# SyringeDriverHW10.net
KiCad netlist of a schematic drawn in Altium Designer
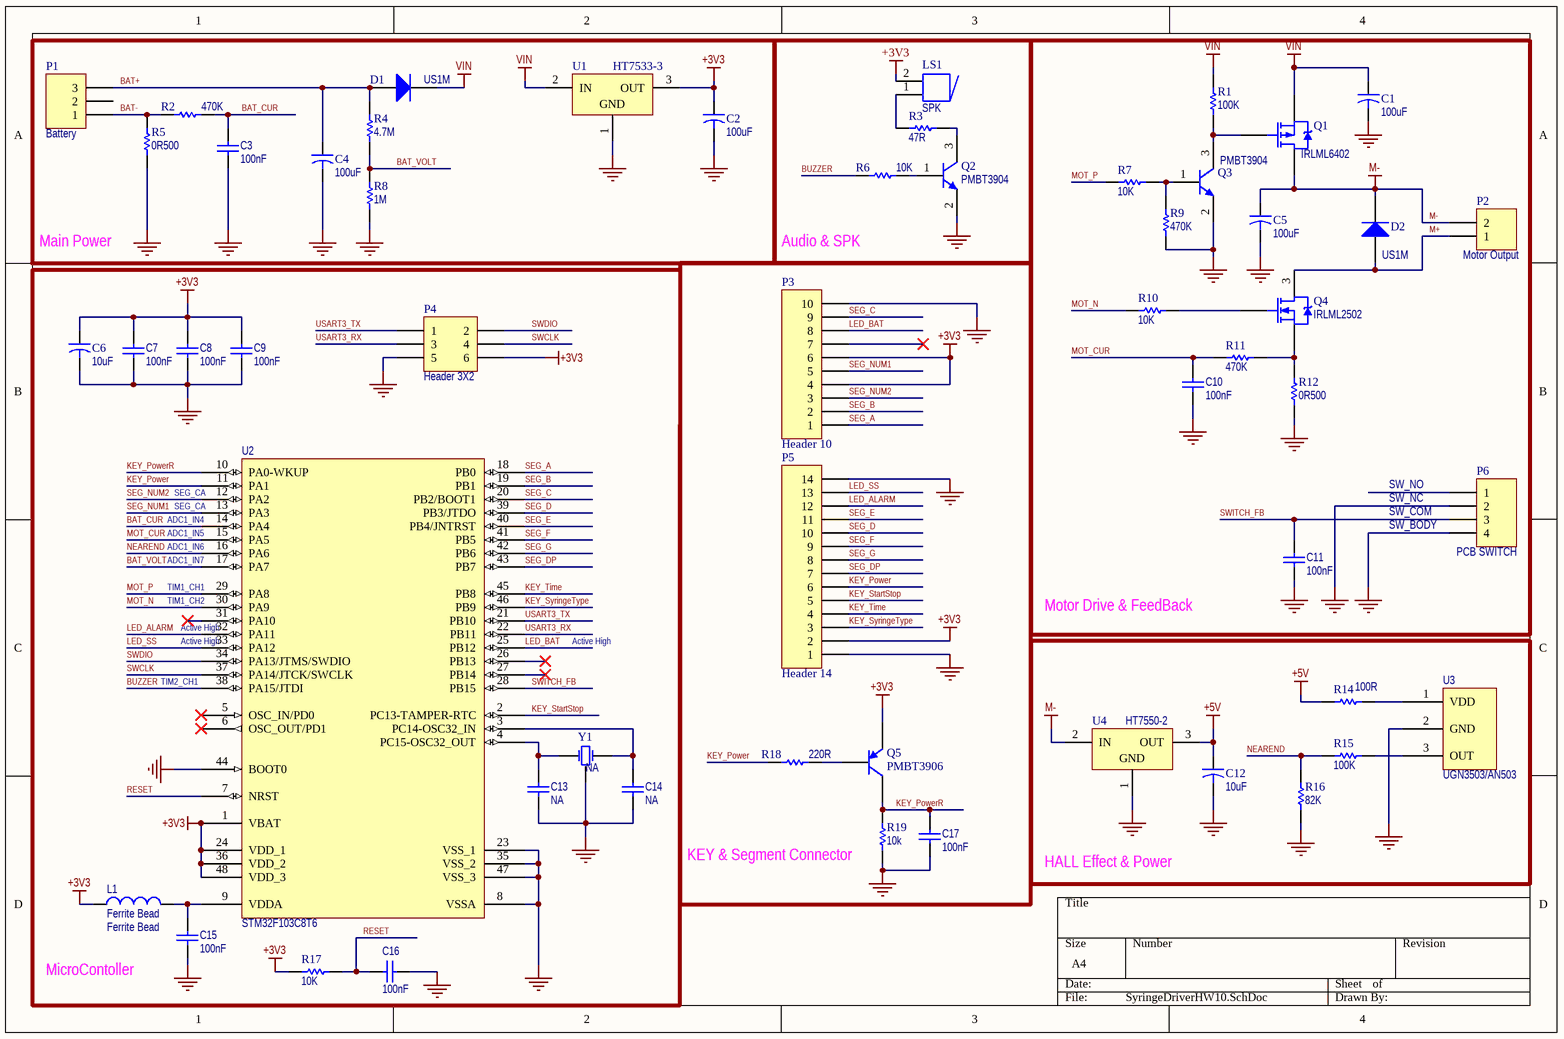
[diagram p0: SyringeDriverHW10.SchDoc]

(export (version "E")
  (design (tool "Eeschema 10.0.6"))
  (components
    (comp (ref "C1")
      (value "100uF")
      (footprint "CAP_EL_SMD_6.3x5.4")
      (description "Electrolyte 16V")
      (fields (field (name "PUBLISHER") "Altium Limited"))
      (libsource (lib "Miscellaneous Devices") (part "Cap2"))
    )
    (comp (ref "C2")
      (value "100uF")
      (footprint "CAP_EL_SMD_6.3x5.4")
      (description "Electrolyte  16V")
      (fields (field (name "PUBLISHER") "Altium Limited"))
      (libsource (lib "Miscellaneous Devices") (part "Cap2"))
    )
    (comp (ref "C3")
      (value "100nF")
      (footprint "CAP0805")
      (description "Capacitor")
      (fields (field (name "PUBLISHER") "Altium Limited"))
      (libsource (lib "Miscellaneous Devices") (part "Cap"))
    )
    (comp (ref "C4")
      (value "100uF")
      (footprint "CAP_EL_SMD_6.3x5.4")
      (description "Electrolyte 16V")
      (fields (field (name "PUBLISHER") "Altium Limited"))
      (libsource (lib "Miscellaneous Devices") (part "Cap2"))
    )
    (comp (ref "C5")
      (value "100uF")
      (footprint "CAP_EL_SMD_6.3x5.4")
      (description "Electrolyte 16V")
      (fields (field (name "PUBLISHER") "Altium Limited"))
      (libsource (lib "Miscellaneous Devices") (part "Cap2"))
    )
    (comp (ref "C6")
      (value "10uF")
      (footprint "CAP_TANTAL_TYPE_A")
      (description "tantal 10V")
      (fields (field (name "PUBLISHER") "Altium Limited"))
      (libsource (lib "Miscellaneous Devices") (part "Cap2"))
    )
    (comp (ref "C7")
      (value "100nF")
      (footprint "CAP0805")
      (description "Capacitor")
      (fields (field (name "PUBLISHER") "Altium Limited"))
      (libsource (lib "Miscellaneous Devices") (part "Cap"))
    )
    (comp (ref "C8")
      (value "100nF")
      (footprint "CAP0805")
      (description "Capacitor")
      (fields (field (name "PUBLISHER") "Altium Limited"))
      (libsource (lib "Miscellaneous Devices") (part "Cap"))
    )
    (comp (ref "C9")
      (value "100nF")
      (footprint "CAP0805")
      (description "Capacitor")
      (fields (field (name "PUBLISHER") "Altium Limited"))
      (libsource (lib "Miscellaneous Devices") (part "Cap"))
    )
    (comp (ref "C10")
      (value "100nF")
      (footprint "CAP0805")
      (description "Capacitor")
      (fields (field (name "PUBLISHER") "Altium Limited"))
      (libsource (lib "Miscellaneous Devices") (part "Cap"))
    )
    (comp (ref "C11")
      (value "100nF")
      (footprint "CAP0805")
      (description "Capacitor")
      (fields (field (name "PUBLISHER") "Altium Limited"))
      (libsource (lib "Miscellaneous Devices") (part "Cap"))
    )
    (comp (ref "C12")
      (value "10uF")
      (footprint "CAP_EL_SMD_4x5.3")
      (description "Electrolyte 10V")
      (fields (field (name "PUBLISHER") "Altium Limited"))
      (libsource (lib "Miscellaneous Devices") (part "Cap2"))
    )
    (comp (ref "C13")
      (value "NA")
      (footprint "CAP0805")
      (description "Capacitor")
      (fields (field (name "PUBLISHER") "Altium Limited"))
      (libsource (lib "Miscellaneous Devices") (part "Cap"))
    )
    (comp (ref "C14")
      (value "NA")
      (footprint "CAP0805")
      (description "Capacitor")
      (fields (field (name "PUBLISHER") "Altium Limited"))
      (libsource (lib "Miscellaneous Devices") (part "Cap"))
    )
    (comp (ref "C15")
      (value "100nF")
      (footprint "CAP0805")
      (description "Capacitor")
      (fields (field (name "PUBLISHER") "Altium Limited"))
      (libsource (lib "Miscellaneous Devices") (part "Cap"))
    )
    (comp (ref "C16")
      (value "100nF")
      (footprint "CAP0805")
      (description "Capacitor")
      (fields (field (name "PUBLISHER") "Altium Limited"))
      (libsource (lib "Miscellaneous Devices") (part "Cap"))
    )
    (comp (ref "C17")
      (value "100nF")
      (footprint "CAP0805")
      (description "Capacitor")
      (fields (field (name "PUBLISHER") "Altium Limited"))
      (libsource (lib "Miscellaneous Devices") (part "Cap"))
    )
    (comp (ref "D1")
      (value "US1M")
      (footprint "DO-241AC")
      (description "1 Amp General Purpose Rectifier")
      (fields (field (name "PUBLISHER") "Altium Limited"))
      (libsource (lib "Miscellaneous Devices") (part "Diode 1N4001"))
    )
    (comp (ref "D2")
      (value "US1M")
      (footprint "DO-241AC")
      (description "1 Amp General Purpose Rectifier")
      (fields (field (name "PUBLISHER") "Altium Limited"))
      (libsource (lib "Miscellaneous Devices") (part "Diode 1N4001"))
    )
    (comp (ref "L1")
      (value "Ferrite Bead")
      (footprint "IND0805")
      (fields (field (name "ALTIUM_VALUE") "Ferrite Bead") (field (name "PUBLISHER") "Altium Limited"))
      (libsource (lib "Miscellaneous Devices") (part "Inductor"))
    )
    (comp (ref "LS1")
      (value "SPK")
      (footprint "XH-2PIN")
      (description "Magnetic Transducer Buzzer")
      (fields (field (name "PUBLISHER") "Altium Limited"))
      (libsource (lib "Miscellaneous Devices") (part "Buzzer"))
    )
    (comp (ref "P1")
      (value "Battery")
      (footprint "XH-3PIN")
      (description "Header, 3-Pin")
      (fields (field (name "PUBLISHER") "Altium Limited"))
      (libsource (lib "Miscellaneous Connectors") (part "Header 3"))
    )
    (comp (ref "P2")
      (value "Motor Output")
      (footprint "XH-2PIN")
      (description "Header, 2-Pin")
      (fields (field (name "PUBLISHER") "Altium Limited"))
      (libsource (lib "Miscellaneous Connectors") (part "Header 2"))
    )
    (comp (ref "P3")
      (value "Header 10")
      (footprint "HDR_1x10-2mm")
      (description "Header, 10-Pin")
      (fields (field (name "PUBLISHER") "Altium Limited"))
      (libsource (lib "Miscellaneous Connectors") (part "Header 10"))
    )
    (comp (ref "P4")
      (value "Header 3X2")
      (footprint "HDR2X3")
      (description "Header, 3-Pin, Dual row")
      (fields (field (name "PUBLISHER") "Altium Limited"))
      (libsource (lib "Miscellaneous Connectors") (part "Header 3X2"))
    )
    (comp (ref "P5")
      (value "Header 14")
      (footprint "HDR_1x14-2mm")
      (description "Header, 14-Pin")
      (fields (field (name "PUBLISHER") "Altium Limited"))
      (libsource (lib "Miscellaneous Connectors") (part "Header 14"))
    )
    (comp (ref "P6")
      (value "PCB SWITCH")
      (footprint "MICROSW_VERTICAL")
      (description "Header, 4-Pin")
      (fields (field (name "PUBLISHER") "Altium Limited"))
      (libsource (lib "Miscellaneous Connectors") (part "Header 4"))
    )
    (comp (ref "Q1")
      (value "IRLML6402")
      (footprint "Micro3_N")
      (description "HEXFET Power MOSFET")
      (fields (field (name "PUBLISHER") "Altium Limited"))
      (libsource (lib "IR Discrete MOSFET - Power") (part "IRLML6401"))
    )
    (comp (ref "Q2")
      (value "PMBT3904")
      (footprint "SOT23_N")
      (description "NPN Switching Transistor")
      (fields (field (name "PUBLISHER") "Altium Limited"))
      (libsource (lib "Philips Discrete BJT - Low Power") (part "PMBT3904"))
    )
    (comp (ref "Q3")
      (value "PMBT3904")
      (footprint "SOT23_N")
      (description "NPN Switching Transistor")
      (fields (field (name "PUBLISHER") "Altium Limited"))
      (libsource (lib "Philips Discrete BJT - Low Power") (part "PMBT3904"))
    )
    (comp (ref "Q4")
      (value "IRLML2502")
      (footprint "SOT-23_N")
      (description "HEXFET Power MOSFET")
      (fields (field (name "PUBLISHER") "Altium Limited"))
      (libsource (lib "IR Discrete MOSFET - Power") (part "IRLML2402"))
    )
    (comp (ref "Q5")
      (value "PMBT3906")
      (footprint "SOT23_N")
      (description "PNP Switching Transistor")
      (fields (field (name "PUBLISHER") "Altium Limited"))
      (libsource (lib "Philips Discrete BJT - Low Power") (part "PMBT3906"))
    )
    (comp (ref "R1")
      (value "100K")
      (footprint "RES0805")
      (description "Resistor")
      (fields (field (name "PUBLISHER") "Altium Limited"))
      (libsource (lib "Miscellaneous Devices") (part "Res1"))
    )
    (comp (ref "R2")
      (value "470K")
      (footprint "RES0805")
      (description "Resistor")
      (fields (field (name "PUBLISHER") "Altium Limited"))
      (libsource (lib "Miscellaneous Devices") (part "Res1"))
    )
    (comp (ref "R3")
      (value "47R")
      (footprint "RES0805")
      (description "Resistor")
      (fields (field (name "PUBLISHER") "Altium Limited"))
      (libsource (lib "Miscellaneous Devices") (part "Res1"))
    )
    (comp (ref "R4")
      (value "4.7M")
      (footprint "RES0805")
      (description "Resistor")
      (fields (field (name "PUBLISHER") "Altium Limited"))
      (libsource (lib "Miscellaneous Devices") (part "Res1"))
    )
    (comp (ref "R5")
      (value "0R500")
      (footprint "RES2512")
      (description "Resistor")
      (fields (field (name "PUBLISHER") "Altium Limited"))
      (libsource (lib "Miscellaneous Devices") (part "Res1"))
    )
    (comp (ref "R6")
      (value "10K")
      (footprint "RES0805")
      (description "Resistor")
      (fields (field (name "PUBLISHER") "Altium Limited"))
      (libsource (lib "Miscellaneous Devices") (part "Res1"))
    )
    (comp (ref "R7")
      (value "10K")
      (footprint "RES0805")
      (description "Resistor")
      (fields (field (name "PUBLISHER") "Altium Limited"))
      (libsource (lib "Miscellaneous Devices") (part "Res1"))
    )
    (comp (ref "R8")
      (value "1M")
      (footprint "RES0805")
      (description "Resistor")
      (fields (field (name "PUBLISHER") "Altium Limited"))
      (libsource (lib "Miscellaneous Devices") (part "Res1"))
    )
    (comp (ref "R9")
      (value "470K")
      (footprint "RES0805")
      (description "Resistor")
      (fields (field (name "PUBLISHER") "Altium Limited"))
      (libsource (lib "Miscellaneous Devices") (part "Res1"))
    )
    (comp (ref "R10")
      (value "10K")
      (footprint "RES0805")
      (description "Resistor")
      (fields (field (name "PUBLISHER") "Altium Limited"))
      (libsource (lib "Miscellaneous Devices") (part "Res1"))
    )
    (comp (ref "R11")
      (value "470K")
      (footprint "RES0805")
      (description "Resistor")
      (fields (field (name "PUBLISHER") "Altium Limited"))
      (libsource (lib "Miscellaneous Devices") (part "Res1"))
    )
    (comp (ref "R12")
      (value "0R500")
      (footprint "RES2512")
      (description "Resistor")
      (fields (field (name "PUBLISHER") "Altium Limited"))
      (libsource (lib "Miscellaneous Devices") (part "Res1"))
    )
    (comp (ref "R14")
      (value "100R")
      (footprint "RES0805")
      (description "Resistor")
      (fields (field (name "PUBLISHER") "Altium Limited"))
      (libsource (lib "Miscellaneous Devices") (part "Res1"))
    )
    (comp (ref "R15")
      (value "100K")
      (footprint "RES0805")
      (description "Resistor")
      (fields (field (name "PUBLISHER") "Altium Limited"))
      (libsource (lib "Miscellaneous Devices") (part "Res1"))
    )
    (comp (ref "R16")
      (value "82K")
      (footprint "RES0805")
      (description "Resistor")
      (fields (field (name "PUBLISHER") "Altium Limited"))
      (libsource (lib "Miscellaneous Devices") (part "Res1"))
    )
    (comp (ref "R17")
      (value "10K")
      (footprint "RES0805")
      (description "Resistor")
      (fields (field (name "PUBLISHER") "Altium Limited"))
      (libsource (lib "Miscellaneous Devices") (part "Res1"))
    )
    (comp (ref "R18")
      (value "220R")
      (footprint "RES0805")
      (description "Resistor")
      (fields (field (name "PUBLISHER") "Altium Limited"))
      (libsource (lib "Miscellaneous Devices") (part "Res1"))
    )
    (comp (ref "R19")
      (value "10k")
      (footprint "RES0805")
      (description "Resistor")
      (fields (field (name "PUBLISHER") "Altium Limited"))
      (libsource (lib "Miscellaneous Devices") (part "Res1"))
    )
    (comp (ref "U1")
      (value "HT7533-3")
      (footprint "SOT89N")
      (description "3.0V 100mA Low Power,  Low Dropout Voltage (LDO) Regulator")
      (fields (field (name "PUBLISHER") "Altium Limited"))
      (libsource (lib "Holtek Power Mgt Voltage Regulator") (part "HT7530-1"))
    )
    (comp (ref "U2")
      (value "STM32F103C8T6")
      (footprint "LQFP48_N")
      (description "STM32 ARM-based 32-bit MCU with 64 Kbytes Flash, 48-pin LQFP, Industrial Temperature")
      (fields (field (name "PUBLISHER") "Altium Limited"))
      (libsource (lib "ST Microcontroller 32-Bit STM32") (part "STM32F103C8T6"))
    )
    (comp (ref "U3")
      (value "UGN3503/AN503")
      (footprint "TO-92 BENT")
      (description "RATIOMETRIC, LINEAR\r\nHALL-EFFECT SENSORS")
      (libsource (lib "Mofidi3D") (part "UGN3503"))
    )
    (comp (ref "U4")
      (value "HT7550-2")
      (footprint "SOT89N")
      (description "5.0V 100mA Low Power,  Low Dropout Voltage (LDO) Regulator")
      (fields (field (name "PUBLISHER") "Altium Limited"))
      (libsource (lib "Holtek Power Mgt Voltage Regulator") (part "HT7530-1"))
    )
    (comp (ref "Y1")
      (value "NA")
      (footprint "Crystal_NC308-RA")
      (description "XTAL Crystal")
      (fields (field (name "DESIGNER") "ABBAS BASEREH"))
      (libsource (lib "Mofidi3D") (part "XTAL_Crystal_G"))
    )
  )
  (nets
    (net (code "1") (name "+3V3") (class "Default")
      (node (ref "C2") (pin "1") (pinfunction "1_1") (pintype "passive"))
      (node (ref "C6") (pin "1") (pinfunction "1_1") (pintype "passive"))
      (node (ref "C7") (pin "2") (pinfunction "2_2") (pintype "passive"))
      (node (ref "C8") (pin "2") (pinfunction "2_2") (pintype "passive"))
      (node (ref "C9") (pin "2") (pinfunction "2_2") (pintype "passive"))
      (node (ref "L1") (pin "1") (pinfunction "1_1") (pintype "passive"))
      (node (ref "LS1") (pin "2") (pinfunction "2_2") (pintype "passive"))
      (node (ref "P3") (pin "4") (pinfunction "4_4") (pintype "passive"))
      (node (ref "P3") (pin "6") (pinfunction "6_6") (pintype "passive"))
      (node (ref "P4") (pin "6") (pinfunction "6_6") (pintype "passive"))
      (node (ref "P5") (pin "2") (pinfunction "2_2") (pintype "passive"))
      (node (ref "Q5") (pin "2") (pinfunction "E_2") (pintype "passive"))
      (node (ref "R17") (pin "2") (pinfunction "2_2") (pintype "passive"))
      (node (ref "U1") (pin "3") (pinfunction "OUT_3") (pintype "power_in"))
      (node (ref "U2") (pin "1") (pinfunction "VBAT_1") (pintype "power_in"))
      (node (ref "U2") (pin "24") (pinfunction "VDD_1_24") (pintype "power_in"))
      (node (ref "U2") (pin "36") (pinfunction "VDD_2_36") (pintype "power_in"))
      (node (ref "U2") (pin "48") (pinfunction "VDD_3_48") (pintype "power_in"))
    )
    (net (code "2") (name "+5V") (class "Default")
      (node (ref "C12") (pin "1") (pinfunction "1_1") (pintype "passive"))
      (node (ref "R14") (pin "1") (pinfunction "1_1") (pintype "passive"))
      (node (ref "U4") (pin "3") (pinfunction "OUT_3") (pintype "power_in"))
    )
    (net (code "3") (name "/BAT+") (class "Default")
      (node (ref "C4") (pin "1") (pinfunction "1_1") (pintype "passive"))
      (node (ref "D1") (pin "1") (pinfunction "A_1") (pintype "passive"))
      (node (ref "P1") (pin "3") (pinfunction "3_3") (pintype "passive"))
      (node (ref "R4") (pin "1") (pinfunction "1_1") (pintype "passive"))
    )
    (net (code "4") (name "/BAT-") (class "Default")
      (node (ref "P1") (pin "1") (pinfunction "1_1") (pintype "passive"))
      (node (ref "R2") (pin "2") (pinfunction "2_2") (pintype "passive"))
      (node (ref "R5") (pin "2") (pinfunction "2_2") (pintype "passive"))
    )
    (net (code "5") (name "/BAT_CUR") (class "Default")
      (node (ref "C3") (pin "2") (pinfunction "2_2") (pintype "passive"))
      (node (ref "R2") (pin "1") (pinfunction "1_1") (pintype "passive"))
      (node (ref "U2") (pin "14") (pinfunction "PA4_14") (pintype "bidirectional"))
    )
    (net (code "6") (name "/BAT_VOLT") (class "Default")
      (node (ref "R4") (pin "2") (pinfunction "2_2") (pintype "passive"))
      (node (ref "R8") (pin "1") (pinfunction "1_1") (pintype "passive"))
      (node (ref "U2") (pin "17") (pinfunction "PA7_17") (pintype "bidirectional"))
    )
    (net (code "7") (name "/BUZZER") (class "Default")
      (node (ref "R6") (pin "2") (pinfunction "2_2") (pintype "passive"))
      (node (ref "U2") (pin "38") (pinfunction "PA15/JTDI_38") (pintype "bidirectional"))
    )
    (net (code "8") (name "/KEY_Power") (class "Default")
      (node (ref "P5") (pin "6") (pinfunction "6_6") (pintype "passive"))
      (node (ref "R18") (pin "1") (pinfunction "1_1") (pintype "passive"))
      (node (ref "U2") (pin "11") (pinfunction "PA1_11") (pintype "bidirectional"))
    )
    (net (code "9") (name "/KEY_PowerR") (class "Default")
      (node (ref "C17") (pin "1") (pinfunction "1_1") (pintype "passive"))
      (node (ref "Q5") (pin "3") (pinfunction "C_3") (pintype "passive"))
      (node (ref "R19") (pin "2") (pinfunction "2_2") (pintype "passive"))
      (node (ref "U2") (pin "10") (pinfunction "PA0-WKUP_10") (pintype "bidirectional"))
    )
    (net (code "10") (name "/KEY_StartStop") (class "Default")
      (node (ref "P5") (pin "5") (pinfunction "5_5") (pintype "passive"))
      (node (ref "U2") (pin "2") (pinfunction "PC13-TAMPER-RTC_2") (pintype "bidirectional"))
    )
    (net (code "11") (name "/KEY_SyringeType") (class "Default")
      (node (ref "P5") (pin "3") (pinfunction "3_3") (pintype "passive"))
      (node (ref "U2") (pin "46") (pinfunction "PB9_46") (pintype "bidirectional"))
    )
    (net (code "12") (name "/KEY_Time") (class "Default")
      (node (ref "P5") (pin "4") (pinfunction "4_4") (pintype "passive"))
      (node (ref "U2") (pin "45") (pinfunction "PB8_45") (pintype "bidirectional"))
    )
    (net (code "13") (name "/LED_ALARM") (class "Default")
      (node (ref "P5") (pin "12") (pinfunction "12_12") (pintype "passive"))
      (node (ref "U2") (pin "32") (pinfunction "PA11_32") (pintype "bidirectional"))
    )
    (net (code "14") (name "/LED_BAT") (class "Default")
      (node (ref "P3") (pin "8") (pinfunction "8_8") (pintype "passive"))
      (node (ref "U2") (pin "25") (pinfunction "PB12_25") (pintype "bidirectional"))
    )
    (net (code "15") (name "/LED_SS") (class "Default")
      (node (ref "P5") (pin "13") (pinfunction "13_13") (pintype "passive"))
      (node (ref "U2") (pin "33") (pinfunction "PA12_33") (pintype "bidirectional"))
    )
    (net (code "16") (name "/M+") (class "Default")
      (node (ref "D2") (pin "1") (pinfunction "A_1") (pintype "passive"))
      (node (ref "P2") (pin "1") (pinfunction "1_1") (pintype "passive"))
      (node (ref "Q4") (pin "3") (pinfunction "D_3") (pintype "passive"))
    )
    (net (code "17") (name "/MOT_CUR") (class "Default")
      (node (ref "C10") (pin "2") (pinfunction "2_2") (pintype "passive"))
      (node (ref "R11") (pin "1") (pinfunction "1_1") (pintype "passive"))
      (node (ref "U2") (pin "15") (pinfunction "PA5_15") (pintype "bidirectional"))
    )
    (net (code "18") (name "/MOT_N") (class "Default")
      (node (ref "R10") (pin "1") (pinfunction "1_1") (pintype "passive"))
      (node (ref "U2") (pin "30") (pinfunction "PA9_30") (pintype "bidirectional"))
    )
    (net (code "19") (name "/MOT_P") (class "Default")
      (node (ref "R7") (pin "1") (pinfunction "1_1") (pintype "passive"))
      (node (ref "U2") (pin "29") (pinfunction "PA8_29") (pintype "bidirectional"))
    )
    (net (code "20") (name "/NEAREND") (class "Default")
      (node (ref "R15") (pin "1") (pinfunction "1_1") (pintype "passive"))
      (node (ref "R16") (pin "2") (pinfunction "2_2") (pintype "passive"))
      (node (ref "U2") (pin "16") (pinfunction "PA6_16") (pintype "bidirectional"))
    )
    (net (code "21") (name "/RESET") (class "Default")
      (node (ref "C16") (pin "2") (pinfunction "2_2") (pintype "passive"))
      (node (ref "R17") (pin "1") (pinfunction "1_1") (pintype "passive"))
      (node (ref "U2") (pin "7") (pinfunction "NRST_7") (pintype "bidirectional"))
    )
    (net (code "22") (name "/SEG_A") (class "Default")
      (node (ref "P3") (pin "1") (pinfunction "1_1") (pintype "passive"))
      (node (ref "U2") (pin "18") (pinfunction "PB0_18") (pintype "bidirectional"))
    )
    (net (code "23") (name "/SEG_B") (class "Default")
      (node (ref "P3") (pin "2") (pinfunction "2_2") (pintype "passive"))
      (node (ref "U2") (pin "19") (pinfunction "PB1_19") (pintype "bidirectional"))
    )
    (net (code "24") (name "/SEG_C") (class "Default")
      (node (ref "P3") (pin "9") (pinfunction "9_9") (pintype "passive"))
      (node (ref "U2") (pin "20") (pinfunction "PB2/BOOT1_20") (pintype "bidirectional"))
    )
    (net (code "25") (name "/SEG_D") (class "Default")
      (node (ref "P5") (pin "10") (pinfunction "10_10") (pintype "passive"))
      (node (ref "U2") (pin "39") (pinfunction "PB3/JTDO_39") (pintype "bidirectional"))
    )
    (net (code "26") (name "/SEG_DP") (class "Default")
      (node (ref "P5") (pin "7") (pinfunction "7_7") (pintype "passive"))
      (node (ref "U2") (pin "43") (pinfunction "PB7_43") (pintype "bidirectional"))
    )
    (net (code "27") (name "/SEG_E") (class "Default")
      (node (ref "P5") (pin "11") (pinfunction "11_11") (pintype "passive"))
      (node (ref "U2") (pin "40") (pinfunction "PB4/JNTRST_40") (pintype "bidirectional"))
    )
    (net (code "28") (name "/SEG_F") (class "Default")
      (node (ref "P5") (pin "9") (pinfunction "9_9") (pintype "passive"))
      (node (ref "U2") (pin "41") (pinfunction "PB5_41") (pintype "bidirectional"))
    )
    (net (code "29") (name "/SEG_G") (class "Default")
      (node (ref "P5") (pin "8") (pinfunction "8_8") (pintype "passive"))
      (node (ref "U2") (pin "42") (pinfunction "PB6_42") (pintype "bidirectional"))
    )
    (net (code "30") (name "/SEG_NUM1") (class "Default")
      (node (ref "P3") (pin "5") (pinfunction "5_5") (pintype "passive"))
      (node (ref "U2") (pin "13") (pinfunction "PA3_13") (pintype "bidirectional"))
    )
    (net (code "31") (name "/SEG_NUM2") (class "Default")
      (node (ref "P3") (pin "3") (pinfunction "3_3") (pintype "passive"))
      (node (ref "U2") (pin "12") (pinfunction "PA2_12") (pintype "bidirectional"))
    )
    (net (code "32") (name "/SWCLK") (class "Default")
      (node (ref "P4") (pin "4") (pinfunction "4_4") (pintype "passive"))
      (node (ref "U2") (pin "37") (pinfunction "PA14/JTCK/SWCLK_37") (pintype "bidirectional"))
    )
    (net (code "33") (name "/SWDIO") (class "Default")
      (node (ref "P4") (pin "2") (pinfunction "2_2") (pintype "passive"))
      (node (ref "U2") (pin "34") (pinfunction "PA13/JTMS/SWDIO_34") (pintype "bidirectional"))
    )
    (net (code "34") (name "/SWITCH_FB") (class "Default")
      (node (ref "C11") (pin "2") (pinfunction "2_2") (pintype "passive"))
      (node (ref "P6") (pin "3") (pinfunction "3_3") (pintype "passive"))
      (node (ref "U2") (pin "28") (pinfunction "PB15_28") (pintype "bidirectional"))
    )
    (net (code "35") (name "/USART3_RX") (class "Default")
      (node (ref "P4") (pin "3") (pinfunction "3_3") (pintype "passive"))
      (node (ref "U2") (pin "22") (pinfunction "PB11_22") (pintype "bidirectional"))
    )
    (net (code "36") (name "/USART3_TX") (class "Default")
      (node (ref "P4") (pin "1") (pinfunction "1_1") (pintype "passive"))
      (node (ref "U2") (pin "21") (pinfunction "PB10_21") (pintype "bidirectional"))
    )
    (net (code "37") (name "GND") (class "Default")
      (node (ref "C1") (pin "2") (pinfunction "2_2") (pintype "passive"))
      (node (ref "C10") (pin "1") (pinfunction "1_1") (pintype "passive"))
      (node (ref "C11") (pin "1") (pinfunction "1_1") (pintype "passive"))
      (node (ref "C12") (pin "2") (pinfunction "2_2") (pintype "passive"))
      (node (ref "C13") (pin "1") (pinfunction "1_1") (pintype "passive"))
      (node (ref "C14") (pin "1") (pinfunction "1_1") (pintype "passive"))
      (node (ref "C15") (pin "1") (pinfunction "1_1") (pintype "passive"))
      (node (ref "C16") (pin "1") (pinfunction "1_1") (pintype "passive"))
      (node (ref "C17") (pin "2") (pinfunction "2_2") (pintype "passive"))
      (node (ref "C2") (pin "2") (pinfunction "2_2") (pintype "passive"))
      (node (ref "C3") (pin "1") (pinfunction "1_1") (pintype "passive"))
      (node (ref "C4") (pin "2") (pinfunction "2_2") (pintype "passive"))
      (node (ref "C5") (pin "2") (pinfunction "2_2") (pintype "passive"))
      (node (ref "C6") (pin "2") (pinfunction "2_2") (pintype "passive"))
      (node (ref "C7") (pin "1") (pinfunction "1_1") (pintype "passive"))
      (node (ref "C8") (pin "1") (pinfunction "1_1") (pintype "passive"))
      (node (ref "C9") (pin "1") (pinfunction "1_1") (pintype "passive"))
      (node (ref "P3") (pin "10") (pinfunction "10_10") (pintype "passive"))
      (node (ref "P4") (pin "5") (pinfunction "5_5") (pintype "passive"))
      (node (ref "P5") (pin "1") (pinfunction "1_1") (pintype "passive"))
      (node (ref "P5") (pin "14") (pinfunction "14_14") (pintype "passive"))
      (node (ref "P6") (pin "2") (pinfunction "2_2") (pintype "passive"))
      (node (ref "P6") (pin "4") (pinfunction "4_4") (pintype "passive"))
      (node (ref "Q2") (pin "2") (pinfunction "E_2") (pintype "passive"))
      (node (ref "Q3") (pin "2") (pinfunction "E_2") (pintype "passive"))
      (node (ref "R12") (pin "1") (pinfunction "1_1") (pintype "passive"))
      (node (ref "R16") (pin "1") (pinfunction "1_1") (pintype "passive"))
      (node (ref "R19") (pin "1") (pinfunction "1_1") (pintype "passive"))
      (node (ref "R5") (pin "1") (pinfunction "1_1") (pintype "passive"))
      (node (ref "R8") (pin "2") (pinfunction "2_2") (pintype "passive"))
      (node (ref "R9") (pin "2") (pinfunction "2_2") (pintype "passive"))
      (node (ref "U1") (pin "1") (pinfunction "GND_1") (pintype "power_in"))
      (node (ref "U2") (pin "23") (pinfunction "VSS_1_23") (pintype "power_in"))
      (node (ref "U2") (pin "35") (pinfunction "VSS_2_35") (pintype "power_in"))
      (node (ref "U2") (pin "44") (pinfunction "BOOT0_44") (pintype "input"))
      (node (ref "U2") (pin "47") (pinfunction "VSS_3_47") (pintype "power_in"))
      (node (ref "U2") (pin "8") (pinfunction "VSSA_8") (pintype "power_in"))
      (node (ref "U3") (pin "2") (pinfunction "GND_2") (pintype "passive"))
      (node (ref "U4") (pin "1") (pinfunction "GND_1") (pintype "power_in"))
      (node (ref "Y1") (pin "3") (pinfunction "GND_3") (pintype "passive"))
    )
    (net (code "38") (name "M-") (class "Default")
      (node (ref "C5") (pin "1") (pinfunction "1_1") (pintype "passive"))
      (node (ref "D2") (pin "2") (pinfunction "K_2") (pintype "passive"))
      (node (ref "P2") (pin "2") (pinfunction "2_2") (pintype "passive"))
      (node (ref "Q1") (pin "3") (pinfunction "D_3") (pintype "passive"))
      (node (ref "U4") (pin "2") (pinfunction "IN_2") (pintype "power_in"))
    )
    (net (code "39") (name "Net-(LS1-Pad1)") (class "Default")
      (node (ref "LS1") (pin "1") (pinfunction "1_1") (pintype "passive"))
      (node (ref "R3") (pin "1") (pinfunction "1_1") (pintype "passive"))
    )
    (net (code "40") (name "Net-(Q1-G)") (class "Default")
      (node (ref "Q1") (pin "1") (pinfunction "G_1") (pintype "passive"))
      (node (ref "Q3") (pin "3") (pinfunction "C_3") (pintype "passive"))
      (node (ref "R1") (pin "2") (pinfunction "2_2") (pintype "passive"))
    )
    (net (code "41") (name "Net-(Q2-B)") (class "Default")
      (node (ref "Q2") (pin "1") (pinfunction "B_1") (pintype "passive"))
      (node (ref "R6") (pin "1") (pinfunction "1_1") (pintype "passive"))
    )
    (net (code "42") (name "Net-(Q2-C)") (class "Default")
      (node (ref "Q2") (pin "3") (pinfunction "C_3") (pintype "passive"))
      (node (ref "R3") (pin "2") (pinfunction "2_2") (pintype "passive"))
    )
    (net (code "43") (name "Net-(Q3-B)") (class "Default")
      (node (ref "Q3") (pin "1") (pinfunction "B_1") (pintype "passive"))
      (node (ref "R7") (pin "2") (pinfunction "2_2") (pintype "passive"))
      (node (ref "R9") (pin "1") (pinfunction "1_1") (pintype "passive"))
    )
    (net (code "44") (name "Net-(Q4-G)") (class "Default")
      (node (ref "Q4") (pin "1") (pinfunction "G_1") (pintype "passive"))
      (node (ref "R10") (pin "2") (pinfunction "2_2") (pintype "passive"))
    )
    (net (code "45") (name "Net-(Q4-S)") (class "Default")
      (node (ref "Q4") (pin "2") (pinfunction "S_2") (pintype "passive"))
      (node (ref "R11") (pin "2") (pinfunction "2_2") (pintype "passive"))
      (node (ref "R12") (pin "2") (pinfunction "2_2") (pintype "passive"))
    )
    (net (code "46") (name "Net-(Q5-B)") (class "Default")
      (node (ref "Q5") (pin "1") (pinfunction "B_1") (pintype "passive"))
      (node (ref "R18") (pin "2") (pinfunction "2_2") (pintype "passive"))
    )
    (net (code "47") (name "Net-(U2-PC14-OSC32_IN)") (class "Default")
      (node (ref "C14") (pin "2") (pinfunction "2_2") (pintype "passive"))
      (node (ref "U2") (pin "3") (pinfunction "PC14-OSC32_IN_3") (pintype "bidirectional"))
      (node (ref "Y1") (pin "2") (pinfunction "OSC2_2") (pintype "passive"))
    )
    (net (code "48") (name "Net-(U2-PC15-OSC32_OUT)") (class "Default")
      (node (ref "C13") (pin "2") (pinfunction "2_2") (pintype "passive"))
      (node (ref "U2") (pin "4") (pinfunction "PC15-OSC32_OUT_4") (pintype "bidirectional"))
      (node (ref "Y1") (pin "1") (pinfunction "OSC1_1") (pintype "passive"))
    )
    (net (code "49") (name "Net-(U2-VDDA)") (class "Default")
      (node (ref "C15") (pin "2") (pinfunction "2_2") (pintype "passive"))
      (node (ref "L1") (pin "2") (pinfunction "2_2") (pintype "passive"))
      (node (ref "U2") (pin "9") (pinfunction "VDDA_9") (pintype "power_in"))
    )
    (net (code "50") (name "Net-(U3-OUT)") (class "Default")
      (node (ref "R15") (pin "2") (pinfunction "2_2") (pintype "passive"))
      (node (ref "U3") (pin "3") (pinfunction "OUT_3") (pintype "passive"))
    )
    (net (code "51") (name "Net-(U3-VDD)") (class "Default")
      (node (ref "R14") (pin "2") (pinfunction "2_2") (pintype "passive"))
      (node (ref "U3") (pin "1") (pinfunction "VDD_1") (pintype "passive"))
    )
    (net (code "52") (name "VIN") (class "Default")
      (node (ref "C1") (pin "1") (pinfunction "1_1") (pintype "passive"))
      (node (ref "D1") (pin "2") (pinfunction "K_2") (pintype "passive"))
      (node (ref "Q1") (pin "2") (pinfunction "S_2") (pintype "passive"))
      (node (ref "R1") (pin "1") (pinfunction "1_1") (pintype "passive"))
      (node (ref "U1") (pin "2") (pinfunction "IN_2") (pintype "power_in"))
    )
    (net (code "53") (name "unconnected-(P1-Pad2)") (class "Default")
      (node (ref "P1") (pin "2") (pinfunction "2_2") (pintype "passive"))
    )
    (net (code "54") (name "unconnected-(P3-Pad7)") (class "Default")
      (node (ref "P3") (pin "7") (pinfunction "7_7") (pintype "passive+no_connect"))
    )
    (net (code "55") (name "unconnected-(P6-Pad1)") (class "Default")
      (node (ref "P6") (pin "1") (pinfunction "1_1") (pintype "passive"))
    )
    (net (code "56") (name "unconnected-(U2-OSC_IN{slash}PD0-Pad5)") (class "Default")
      (node (ref "U2") (pin "5") (pinfunction "OSC_IN/PD0_5") (pintype "input+no_connect"))
    )
    (net (code "57") (name "unconnected-(U2-OSC_OUT{slash}PD1-Pad6)") (class "Default")
      (node (ref "U2") (pin "6") (pinfunction "OSC_OUT/PD1_6") (pintype "output+no_connect"))
    )
    (net (code "58") (name "unconnected-(U2-PA10-Pad31)") (class "Default")
      (node (ref "U2") (pin "31") (pinfunction "PA10_31") (pintype "bidirectional+no_connect"))
    )
    (net (code "59") (name "unconnected-(U2-PB13-Pad26)") (class "Default")
      (node (ref "U2") (pin "26") (pinfunction "PB13_26") (pintype "bidirectional+no_connect"))
    )
    (net (code "60") (name "unconnected-(U2-PB14-Pad27)") (class "Default")
      (node (ref "U2") (pin "27") (pinfunction "PB14_27") (pintype "bidirectional+no_connect"))
    )
  )
)
